# relay10.net
KiCad netlist of a schematic drawn in EAGLE
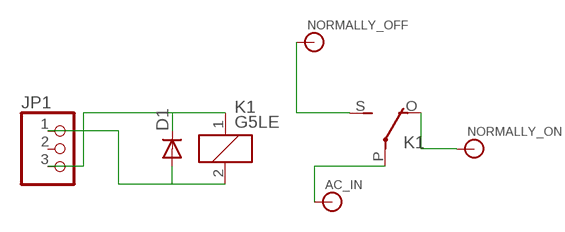
[diagram p0: schematic, sheet 1]

(export (version "E")
  (design (tool "Eeschema 10.0.6"))
  (components
    (comp (ref "AC_IN")
      (value "BANANA_CONN")
      (footprint "eagle-import:BANANA_CONN")
      (libsource (lib "eagle-import") (part "BANANA_CONN"))
    )
    (comp (ref "D1")
      (value "1N4004")
      (footprint "eagle-import:DO41-10")
      (libsource (lib "eagle-import") (part "1N4004"))
    )
    (comp (ref "JP1")
      (value "PINHD-1X3")
      (footprint "eagle-import:1X03")
      (libsource (lib "eagle-import") (part "PINHD-1X3"))
    )
    (comp (ref "K1")
      (value "G5LE")
      (footprint "eagle-import:G5LE")
      (libsource (lib "eagle-import") (part "G5LE"))
    )
    (comp (ref "NORMALLY_OFF")
      (value "BANANA_CONN")
      (footprint "eagle-import:BANANA_CONN")
      (libsource (lib "eagle-import") (part "BANANA_CONN"))
    )
    (comp (ref "NORMALLY_ON")
      (value "BANANA_CONN")
      (footprint "eagle-import:BANANA_CONN")
      (libsource (lib "eagle-import") (part "BANANA_CONN"))
    )
  )
  (nets
    (net (code "1") (name "Net-(AC_IN-1)") (class "Default")
      (node (ref "AC_IN") (pin "P$1") (pinfunction "1_P$1") (pintype "passive"))
      (node (ref "K1") (pin "P") (pinfunction "P_P") (pintype "passive"))
    )
    (net (code "2") (name "Net-(D1-PadA)") (class "Default")
      (node (ref "D1") (pin "A") (pinfunction "A_A") (pintype "passive"))
      (node (ref "JP1") (pin "1") (pinfunction "1_1") (pintype "passive"))
      (node (ref "K1") (pin "2") (pinfunction "2_2") (pintype "passive"))
    )
    (net (code "3") (name "Net-(D1-PadC)") (class "Default")
      (node (ref "D1") (pin "C") (pinfunction "C_C") (pintype "passive"))
      (node (ref "JP1") (pin "3") (pinfunction "3_3") (pintype "passive"))
      (node (ref "K1") (pin "1") (pinfunction "1_1") (pintype "passive"))
    )
    (net (code "4") (name "Net-(NORMALLY_OFF-1)") (class "Default")
      (node (ref "K1") (pin "S") (pinfunction "S_S") (pintype "passive"))
      (node (ref "NORMALLY_OFF") (pin "P$1") (pinfunction "1_P$1") (pintype "passive"))
    )
    (net (code "5") (name "Net-(NORMALLY_ON-1)") (class "Default")
      (node (ref "K1") (pin "O") (pinfunction "O_O") (pintype "passive"))
      (node (ref "NORMALLY_ON") (pin "P$1") (pinfunction "1_P$1") (pintype "passive"))
    )
    (net (code "6") (name "unconnected-(JP1-Pad2)") (class "Default")
      (node (ref "JP1") (pin "2") (pinfunction "2_2") (pintype "passive"))
    )
  )
)
